# board.net
KiCad netlist of a schematic drawn in EAGLE
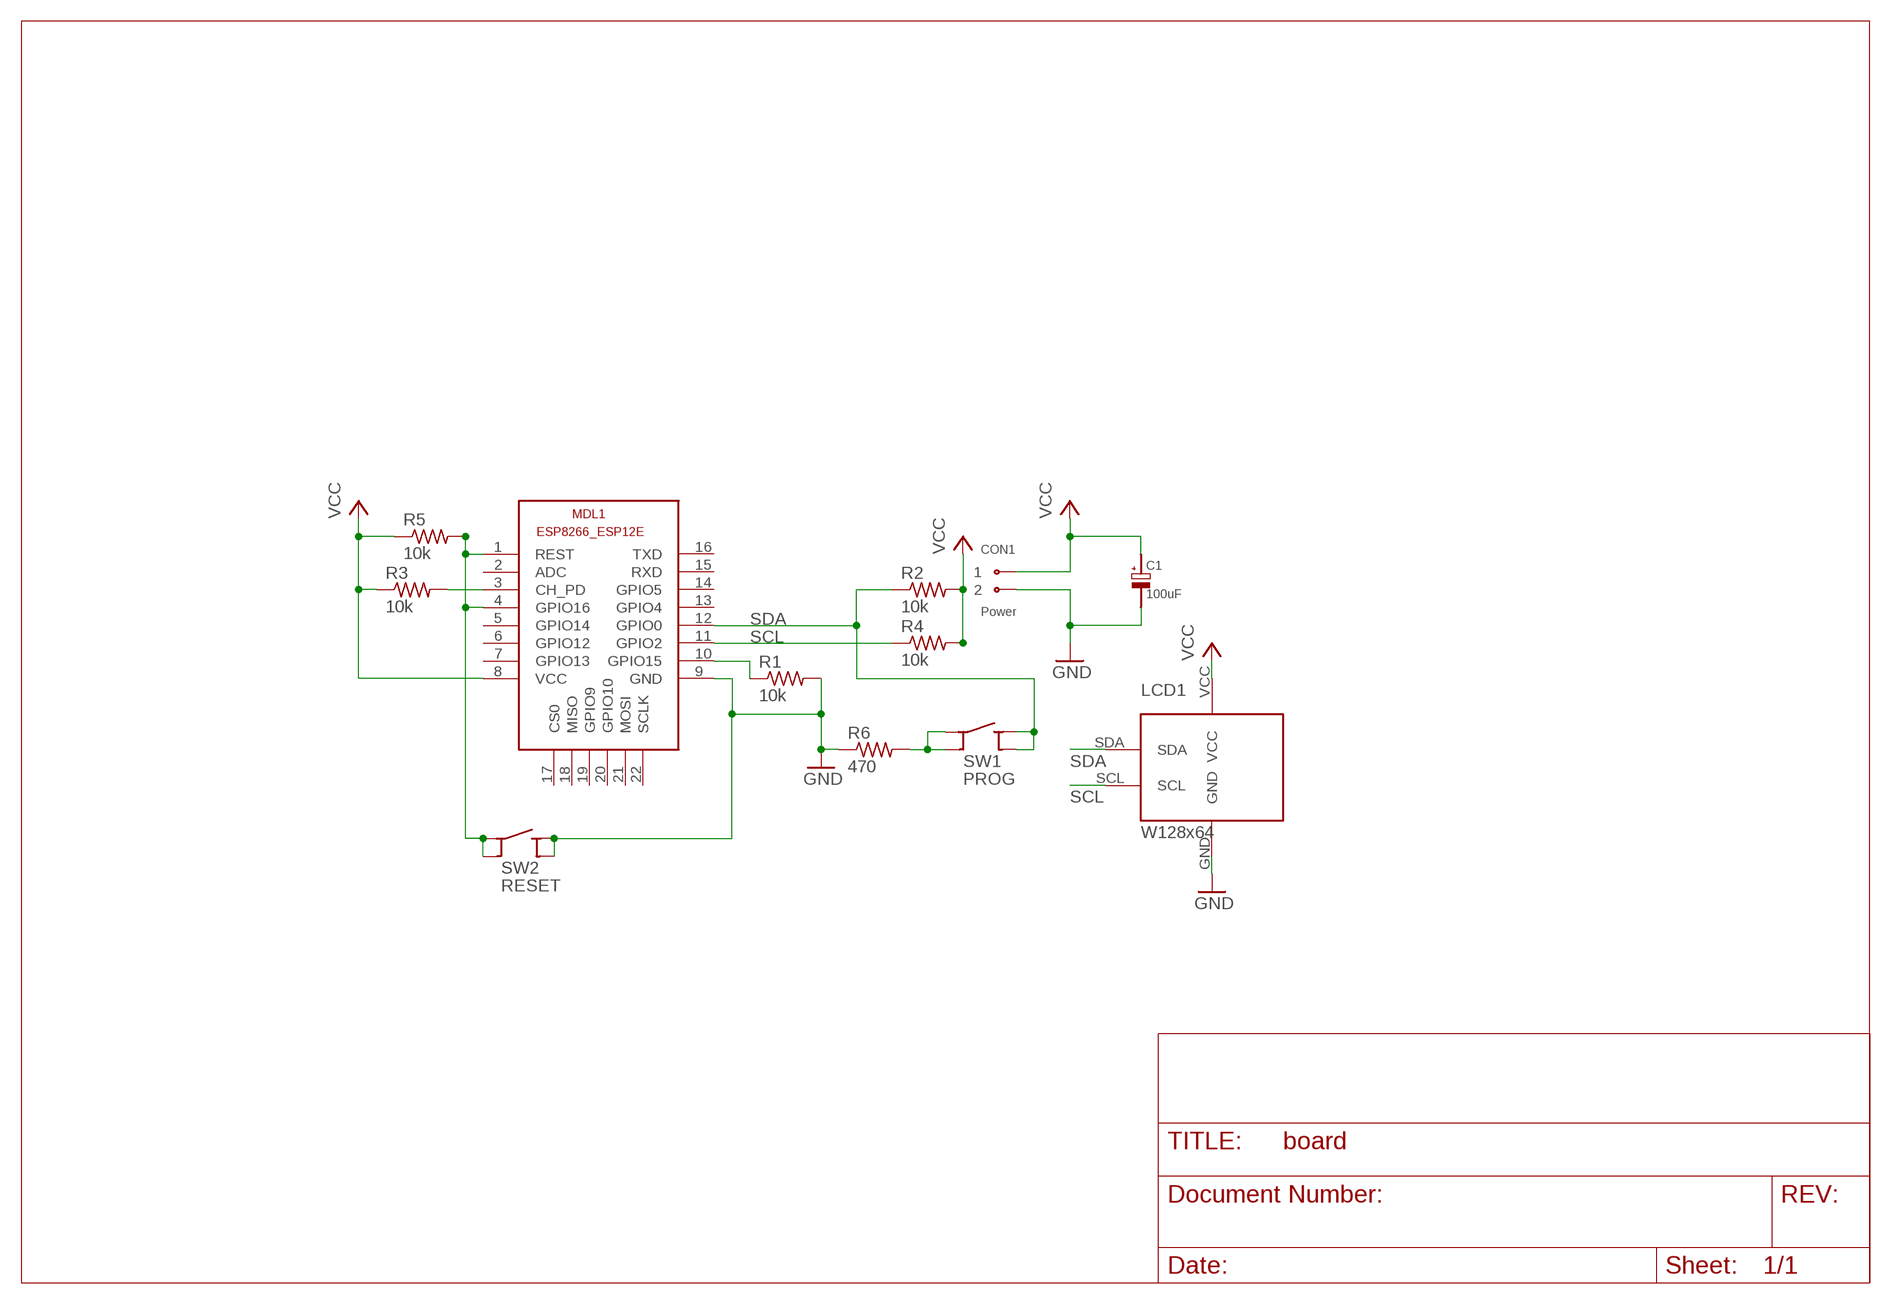
[diagram p0: schematic, sheet 1]

(export (version "E")
  (design (tool "Eeschema 10.0.6"))
  (components
    (comp (ref "C1")
      (value "100uF")
      (footprint "eagle-import:POLTANT02")
      (libsource (lib "eagle-import") (part "CPOLTANT02"))
    )
    (comp (ref "CON1")
      (value "Power")
      (footprint "eagle-import:CON-WEID-PCB2")
      (libsource (lib "eagle-import") (part "CON-1X2WEID-PCB"))
    )
    (comp (ref "LCD1")
      (value "W128x64")
      (footprint "eagle-import:OLED_SMALL_I2C")
      (libsource (lib "eagle-import") (part "OLED_64X128"))
    )
    (comp (ref "MDL1")
      (value "ESP8266")
      (footprint "eagle-import:ESP8266-ESP12E")
      (libsource (lib "eagle-import") (part "ESP8266-12EESP8266-ESP12E"))
    )
    (comp (ref "R1")
      (value "10k")
      (footprint "eagle-import:R0805")
      (libsource (lib "eagle-import") (part "R-US_R0805"))
    )
    (comp (ref "R2")
      (value "10k")
      (footprint "eagle-import:R0805")
      (libsource (lib "eagle-import") (part "R-US_R0805"))
    )
    (comp (ref "R3")
      (value "10k")
      (footprint "eagle-import:R0805")
      (libsource (lib "eagle-import") (part "R-US_R0805"))
    )
    (comp (ref "R4")
      (value "10k")
      (footprint "eagle-import:R0805")
      (libsource (lib "eagle-import") (part "R-US_R0805"))
    )
    (comp (ref "R5")
      (value "10k")
      (footprint "eagle-import:R0805")
      (libsource (lib "eagle-import") (part "R-US_R0805"))
    )
    (comp (ref "R6")
      (value "470")
      (footprint "eagle-import:R0805")
      (libsource (lib "eagle-import") (part "R-US_R0805"))
    )
    (comp (ref "SW1")
      (value "PROG")
      (footprint "eagle-import:SWITCH-SPST-MOMENTARY")
      (libsource (lib "eagle-import") (part "SWITCH-PUSHBUTTONJAYCAR"))
    )
    (comp (ref "SW2")
      (value "RESET")
      (footprint "eagle-import:SWITCH-SPST-MOMENTARY")
      (libsource (lib "eagle-import") (part "SWITCH-PUSHBUTTONJAYCAR"))
    )
  )
  (nets
    (net (code "1") (name "/SCL") (class "Default")
      (node (ref "LCD1") (pin "SCL") (pinfunction "SCL_SCL") (pintype "bidirectional"))
      (node (ref "MDL1") (pin "11") (pinfunction "GPIO2_11") (pintype "bidirectional"))
      (node (ref "R4") (pin "1") (pinfunction "1_1") (pintype "passive"))
    )
    (net (code "2") (name "/SDA") (class "Default")
      (node (ref "LCD1") (pin "SDA") (pinfunction "SDA_SDA") (pintype "bidirectional"))
      (node (ref "MDL1") (pin "12") (pinfunction "GPIO0_12") (pintype "bidirectional"))
      (node (ref "R2") (pin "1") (pinfunction "1_1") (pintype "passive"))
      (node (ref "SW1") (pin "P$3") (pinfunction "P$3_P$3") (pintype "passive"))
      (node (ref "SW1") (pin "P$4") (pinfunction "P$4_P$4") (pintype "passive"))
    )
    (net (code "3") (name "GND") (class "Default")
      (node (ref "C1") (pin "MINUS") (pinfunction "NEGATIVE_MINUS") (pintype "passive"))
      (node (ref "CON1") (pin "2") (pinfunction "2_2") (pintype "passive"))
      (node (ref "LCD1") (pin "GND") (pinfunction "GND_GND") (pintype "power_in"))
      (node (ref "MDL1") (pin "9") (pinfunction "GND_9") (pintype "bidirectional"))
      (node (ref "R1") (pin "2") (pinfunction "2_2") (pintype "passive"))
      (node (ref "R6") (pin "1") (pinfunction "1_1") (pintype "passive"))
      (node (ref "SW2") (pin "P$3") (pinfunction "P$3_P$3") (pintype "passive"))
      (node (ref "SW2") (pin "P$4") (pinfunction "P$4_P$4") (pintype "passive"))
    )
    (net (code "4") (name "Net-(MDL1-CH_PD)") (class "Default")
      (node (ref "MDL1") (pin "3") (pinfunction "CH_PD_3") (pintype "bidirectional"))
      (node (ref "R3") (pin "2") (pinfunction "2_2") (pintype "passive"))
    )
    (net (code "5") (name "Net-(MDL1-GPIO15)") (class "Default")
      (node (ref "MDL1") (pin "10") (pinfunction "GPIO15_10") (pintype "bidirectional"))
      (node (ref "R1") (pin "1") (pinfunction "1_1") (pintype "passive"))
    )
    (net (code "6") (name "Net-(MDL1-GPIO16)") (class "Default")
      (node (ref "MDL1") (pin "1") (pinfunction "REST_1") (pintype "bidirectional"))
      (node (ref "MDL1") (pin "4") (pinfunction "GPIO16_4") (pintype "bidirectional"))
      (node (ref "R5") (pin "2") (pinfunction "2_2") (pintype "passive"))
      (node (ref "SW2") (pin "P$1") (pinfunction "P$1_P$1") (pintype "passive"))
      (node (ref "SW2") (pin "P$2") (pinfunction "P$2_P$2") (pintype "passive"))
    )
    (net (code "7") (name "Net-(R6-Pad2)") (class "Default")
      (node (ref "R6") (pin "2") (pinfunction "2_2") (pintype "passive"))
      (node (ref "SW1") (pin "P$1") (pinfunction "P$1_P$1") (pintype "passive"))
      (node (ref "SW1") (pin "P$2") (pinfunction "P$2_P$2") (pintype "passive"))
    )
    (net (code "8") (name "VCC") (class "Default")
      (node (ref "C1") (pin "PLUS") (pinfunction "POSITIVE_PLUS") (pintype "passive"))
      (node (ref "CON1") (pin "1") (pinfunction "1_1") (pintype "passive"))
      (node (ref "LCD1") (pin "VCC") (pinfunction "VCC_VCC") (pintype "power_in"))
      (node (ref "MDL1") (pin "8") (pinfunction "VCC_8") (pintype "bidirectional"))
      (node (ref "R2") (pin "2") (pinfunction "2_2") (pintype "passive"))
      (node (ref "R3") (pin "1") (pinfunction "1_1") (pintype "passive"))
      (node (ref "R4") (pin "2") (pinfunction "2_2") (pintype "passive"))
      (node (ref "R5") (pin "1") (pinfunction "1_1") (pintype "passive"))
    )
    (net (code "9") (name "unconnected-(MDL1-ADC-Pad2)") (class "Default")
      (node (ref "MDL1") (pin "2") (pinfunction "ADC_2") (pintype "bidirectional"))
    )
    (net (code "10") (name "unconnected-(MDL1-CS0-Pad17)") (class "Default")
      (node (ref "MDL1") (pin "17") (pinfunction "CS0_17") (pintype "bidirectional"))
    )
    (net (code "11") (name "unconnected-(MDL1-GPIO4-Pad13)") (class "Default")
      (node (ref "MDL1") (pin "13") (pinfunction "GPIO4_13") (pintype "bidirectional"))
    )
    (net (code "12") (name "unconnected-(MDL1-GPIO5-Pad14)") (class "Default")
      (node (ref "MDL1") (pin "14") (pinfunction "GPIO5_14") (pintype "bidirectional"))
    )
    (net (code "13") (name "unconnected-(MDL1-GPIO9-Pad19)") (class "Default")
      (node (ref "MDL1") (pin "19") (pinfunction "GPIO9_19") (pintype "bidirectional"))
    )
    (net (code "14") (name "unconnected-(MDL1-GPIO10-Pad20)") (class "Default")
      (node (ref "MDL1") (pin "20") (pinfunction "GPIO10_20") (pintype "bidirectional"))
    )
    (net (code "15") (name "unconnected-(MDL1-GPIO12-Pad6)") (class "Default")
      (node (ref "MDL1") (pin "6") (pinfunction "GPIO12_6") (pintype "bidirectional"))
    )
    (net (code "16") (name "unconnected-(MDL1-GPIO13-Pad7)") (class "Default")
      (node (ref "MDL1") (pin "7") (pinfunction "GPIO13_7") (pintype "bidirectional"))
    )
    (net (code "17") (name "unconnected-(MDL1-GPIO14-Pad5)") (class "Default")
      (node (ref "MDL1") (pin "5") (pinfunction "GPIO14_5") (pintype "bidirectional"))
    )
    (net (code "18") (name "unconnected-(MDL1-MISO-Pad18)") (class "Default")
      (node (ref "MDL1") (pin "18") (pinfunction "MISO_18") (pintype "bidirectional"))
    )
    (net (code "19") (name "unconnected-(MDL1-MOSI-Pad21)") (class "Default")
      (node (ref "MDL1") (pin "21") (pinfunction "MOSI_21") (pintype "bidirectional"))
    )
    (net (code "20") (name "unconnected-(MDL1-RXD-Pad15)") (class "Default")
      (node (ref "MDL1") (pin "15") (pinfunction "RXD_15") (pintype "bidirectional"))
    )
    (net (code "21") (name "unconnected-(MDL1-SCLK-Pad22)") (class "Default")
      (node (ref "MDL1") (pin "22") (pinfunction "SCLK_22") (pintype "bidirectional"))
    )
    (net (code "22") (name "unconnected-(MDL1-TXD-Pad16)") (class "Default")
      (node (ref "MDL1") (pin "16") (pinfunction "TXD_16") (pintype "bidirectional"))
    )
  )
)
